# SOIC14.net
KiCad netlist of a schematic drawn in EAGLE
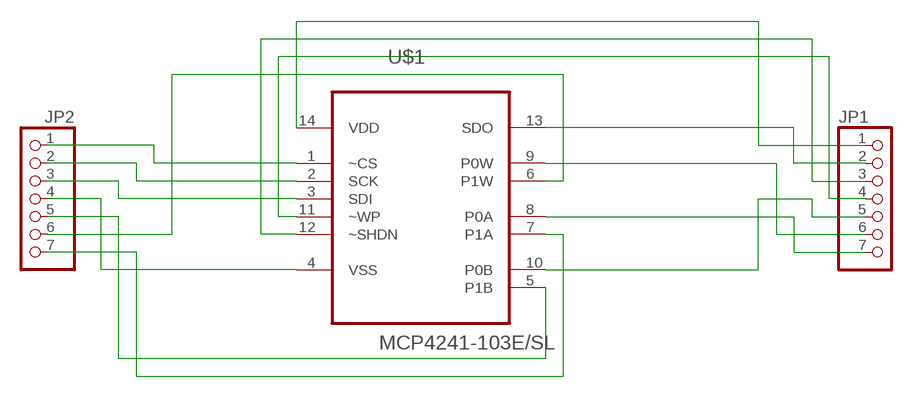
[diagram p0: schematic, sheet 1]

(export (version "E")
  (design (tool "Eeschema 10.0.6"))
  (components
    (comp (ref "JP1")
      (value "PINHD-1X7")
      (footprint "eagle-import:1X07")
      (libsource (lib "eagle-import") (part "PINHD-1X7"))
    )
    (comp (ref "JP2")
      (value "PINHD-1X7")
      (footprint "eagle-import:1X07")
      (libsource (lib "eagle-import") (part "PINHD-1X7"))
    )
    (comp (ref "U$1")
      (value "MCP4241-103E/SL")
      (footprint "eagle-import:SOIC127P600X175-14N")
      (libsource (lib "eagle-import") (part "MCP4241-103E/SL"))
    )
  )
  (nets
    (net (code "1") (name "Net-(U$1-P0A)") (class "Default")
      (node (ref "JP1") (pin "7") (pinfunction "7_7") (pintype "passive"))
      (node (ref "U$1") (pin "8") (pinfunction "P0A_8") (pintype "bidirectional"))
    )
    (net (code "2") (name "Net-(U$1-P0B)") (class "Default")
      (node (ref "JP1") (pin "5") (pinfunction "5_5") (pintype "passive"))
      (node (ref "U$1") (pin "10") (pinfunction "P0B_10") (pintype "bidirectional"))
    )
    (net (code "3") (name "Net-(U$1-P0W)") (class "Default")
      (node (ref "JP1") (pin "6") (pinfunction "6_6") (pintype "passive"))
      (node (ref "U$1") (pin "9") (pinfunction "P0W_9") (pintype "bidirectional"))
    )
    (net (code "4") (name "Net-(U$1-P1A)") (class "Default")
      (node (ref "JP2") (pin "7") (pinfunction "7_7") (pintype "passive"))
      (node (ref "U$1") (pin "7") (pinfunction "P1A_7") (pintype "bidirectional"))
    )
    (net (code "5") (name "Net-(U$1-P1B)") (class "Default")
      (node (ref "JP2") (pin "5") (pinfunction "5_5") (pintype "passive"))
      (node (ref "U$1") (pin "5") (pinfunction "P1B_5") (pintype "bidirectional"))
    )
    (net (code "6") (name "Net-(U$1-P1W)") (class "Default")
      (node (ref "JP2") (pin "6") (pinfunction "6_6") (pintype "passive"))
      (node (ref "U$1") (pin "6") (pinfunction "P1W_6") (pintype "bidirectional"))
    )
    (net (code "7") (name "Net-(U$1-SCK)") (class "Default")
      (node (ref "JP2") (pin "2") (pinfunction "2_2") (pintype "passive"))
      (node (ref "U$1") (pin "2") (pinfunction "SCK_2") (pintype "input"))
    )
    (net (code "8") (name "Net-(U$1-SDI)") (class "Default")
      (node (ref "JP2") (pin "3") (pinfunction "3_3") (pintype "passive"))
      (node (ref "U$1") (pin "3") (pinfunction "SDI_3") (pintype "input"))
    )
    (net (code "9") (name "Net-(U$1-SDO)") (class "Default")
      (node (ref "JP1") (pin "2") (pinfunction "2_2") (pintype "passive"))
      (node (ref "U$1") (pin "13") (pinfunction "SDO_13") (pintype "output"))
    )
    (net (code "10") (name "Net-(U$1-VDD)") (class "Default")
      (node (ref "JP1") (pin "1") (pinfunction "1_1") (pintype "passive"))
      (node (ref "U$1") (pin "14") (pinfunction "VDD_14") (pintype "power_in"))
    )
    (net (code "11") (name "Net-(U$1-VSS)") (class "Default")
      (node (ref "JP2") (pin "4") (pinfunction "4_4") (pintype "passive"))
      (node (ref "U$1") (pin "4") (pinfunction "VSS_4") (pintype "power_in"))
    )
    (net (code "12") (name "Net-(U$1-~{CS})") (class "Default")
      (node (ref "JP2") (pin "1") (pinfunction "1_1") (pintype "passive"))
      (node (ref "U$1") (pin "1") (pinfunction "~{CS}_1") (pintype "input"))
    )
    (net (code "13") (name "Net-(U$1-~{SHDN})") (class "Default")
      (node (ref "JP1") (pin "3") (pinfunction "3_3") (pintype "passive"))
      (node (ref "U$1") (pin "12") (pinfunction "~{SHDN}_12") (pintype "input"))
    )
    (net (code "14") (name "Net-(U$1-~{WP})") (class "Default")
      (node (ref "JP1") (pin "4") (pinfunction "4_4") (pintype "passive"))
      (node (ref "U$1") (pin "11") (pinfunction "~{WP}_11") (pintype "input"))
    )
  )
)
